# arm_sheet.net
KiCad netlist of a schematic drawn in Altium Designer
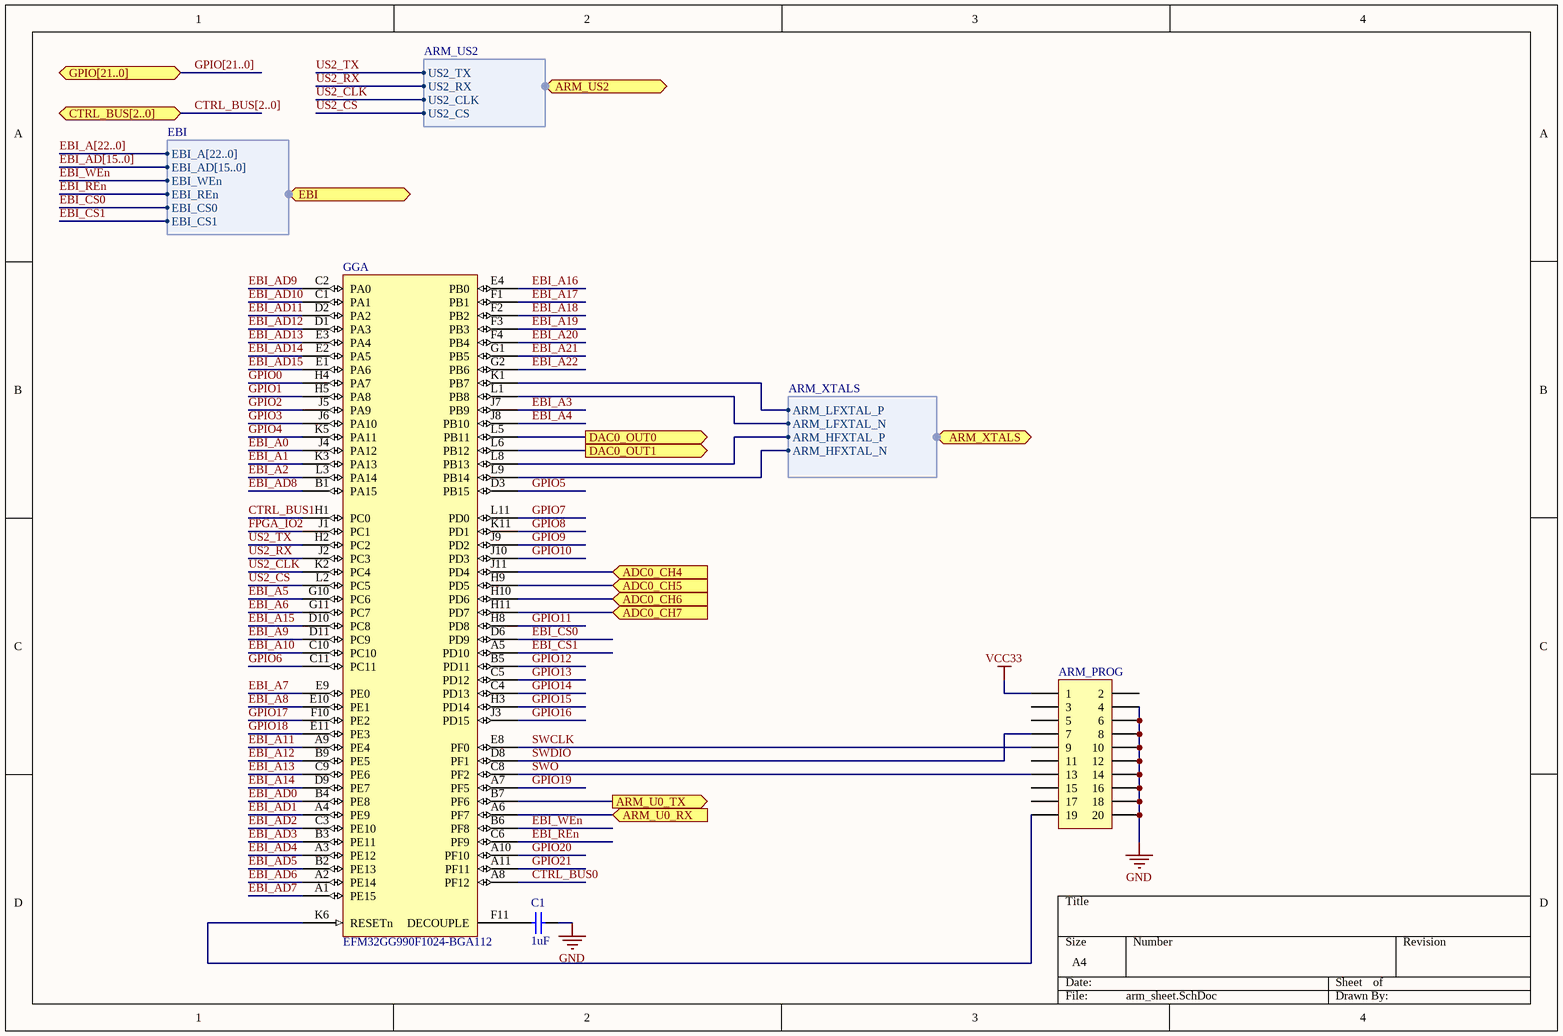
[diagram p0: arm_sheet.SchDoc]

(export (version "E")
  (design (tool "Eeschema 10.0.6"))
  (components
    (comp (ref "ARM_PROG")
      (value "Header 10X2")
      (footprint "HDR2X10")
      (description "Header, 10-Pin, Dual row")
      (fields (field (name "PUBLISHER") "Altium Limited"))
      (libsource (lib "Miscellaneous Connectors") (part "Header 10X2"))
    )
    (comp (ref "C1")
      (value "1uF")
      (footprint "CAPC0805(2012)100_N")
      (description "CAP 1uF 16V ±10% 0805 (2012 Metric) Thickness 1mm SMD")
      (fields (field (name "TOLERANCE") "±10%"))
      (libsource (lib "Altium Content Vault") (part "CMP-1036-04747-1"))
    )
    (comp (ref "GG")
      (value "EFM32GG990F1024-BGA112")
      (footprint "ENMR-BGA112")
      (fields (field (name "GENERIC PART NUMBER") "EFM32GG990"))
      (libsource (lib "Silicon Labs Energy Micro EFM32") (part "EFM32GG990F1024-BGA112"))
    )
  )
  (nets
    (net (code "5") (name "/ADC0_CH4") (class "Default")
      (node (ref "GG") (pin "J11") (pinfunction "PD4_J11") (pintype "bidirectional"))
    )
    (net (code "6") (name "/ADC0_CH5") (class "Default")
      (node (ref "GG") (pin "H9") (pinfunction "PD5_H9") (pintype "bidirectional"))
    )
    (net (code "7") (name "/ADC0_CH6") (class "Default")
      (node (ref "GG") (pin "H10") (pinfunction "PD6_H10") (pintype "bidirectional"))
    )
    (net (code "8") (name "/ADC0_CH7") (class "Default")
      (node (ref "GG") (pin "H11") (pinfunction "PD7_H11") (pintype "bidirectional"))
    )
    (net (code "9") (name "/ARM_HFXTAL_N") (class "Default")
      (node (ref "GG") (pin "L9") (pinfunction "PB14_L9") (pintype "bidirectional"))
    )
    (net (code "10") (name "/ARM_HFXTAL_P") (class "Default")
      (node (ref "GG") (pin "L8") (pinfunction "PB13_L8") (pintype "bidirectional"))
    )
    (net (code "11") (name "/ARM_LFXTAL_N") (class "Default")
      (node (ref "GG") (pin "L1") (pinfunction "PB8_L1") (pintype "bidirectional"))
    )
    (net (code "12") (name "/ARM_LFXTAL_P") (class "Default")
      (node (ref "GG") (pin "K1") (pinfunction "PB7_K1") (pintype "bidirectional"))
    )
    (net (code "13") (name "/ARM_U0_RX") (class "Default")
      (node (ref "GG") (pin "A6") (pinfunction "PF7_A6") (pintype "bidirectional"))
    )
    (net (code "14") (name "/ARM_U0_TX") (class "Default")
      (node (ref "GG") (pin "B7") (pinfunction "PF6_B7") (pintype "bidirectional"))
    )
    (net (code "15") (name "/CTRL_BUS0") (class "Default")
      (node (ref "GG") (pin "A8") (pinfunction "PF12_A8") (pintype "bidirectional"))
    )
    (net (code "16") (name "/CTRL_BUS1") (class "Default")
      (node (ref "GG") (pin "H1") (pinfunction "PC0_H1") (pintype "bidirectional"))
    )
    (net (code "18") (name "/DAC0_OUT0") (class "Default")
      (node (ref "GG") (pin "L5") (pinfunction "PB11_L5") (pintype "bidirectional"))
    )
    (net (code "19") (name "/DAC0_OUT1") (class "Default")
      (node (ref "GG") (pin "L6") (pinfunction "PB12_L6") (pintype "bidirectional"))
    )
    (net (code "20") (name "/EBI_A0") (class "Default")
      (node (ref "GG") (pin "J4") (pinfunction "PA12_J4") (pintype "bidirectional"))
    )
    (net (code "21") (name "/EBI_A1") (class "Default")
      (node (ref "GG") (pin "K3") (pinfunction "PA13_K3") (pintype "bidirectional"))
    )
    (net (code "22") (name "/EBI_A2") (class "Default")
      (node (ref "GG") (pin "L3") (pinfunction "PA14_L3") (pintype "bidirectional"))
    )
    (net (code "23") (name "/EBI_A3") (class "Default")
      (node (ref "GG") (pin "J7") (pinfunction "PB9_J7") (pintype "bidirectional"))
    )
    (net (code "24") (name "/EBI_A4") (class "Default")
      (node (ref "GG") (pin "J8") (pinfunction "PB10_J8") (pintype "bidirectional"))
    )
    (net (code "25") (name "/EBI_A5") (class "Default")
      (node (ref "GG") (pin "G10") (pinfunction "PC6_G10") (pintype "bidirectional"))
    )
    (net (code "26") (name "/EBI_A6") (class "Default")
      (node (ref "GG") (pin "G11") (pinfunction "PC7_G11") (pintype "bidirectional"))
    )
    (net (code "27") (name "/EBI_A7") (class "Default")
      (node (ref "GG") (pin "E9") (pinfunction "PE0_E9") (pintype "bidirectional"))
    )
    (net (code "28") (name "/EBI_A8") (class "Default")
      (node (ref "GG") (pin "E10") (pinfunction "PE1_E10") (pintype "bidirectional"))
    )
    (net (code "29") (name "/EBI_A9") (class "Default")
      (node (ref "GG") (pin "D11") (pinfunction "PC9_D11") (pintype "bidirectional"))
    )
    (net (code "30") (name "/EBI_A10") (class "Default")
      (node (ref "GG") (pin "C10") (pinfunction "PC10_C10") (pintype "bidirectional"))
    )
    (net (code "31") (name "/EBI_A11") (class "Default")
      (node (ref "GG") (pin "A9") (pinfunction "PE4_A9") (pintype "bidirectional"))
    )
    (net (code "32") (name "/EBI_A12") (class "Default")
      (node (ref "GG") (pin "B9") (pinfunction "PE5_B9") (pintype "bidirectional"))
    )
    (net (code "33") (name "/EBI_A13") (class "Default")
      (node (ref "GG") (pin "C9") (pinfunction "PE6_C9") (pintype "bidirectional"))
    )
    (net (code "34") (name "/EBI_A14") (class "Default")
      (node (ref "GG") (pin "D9") (pinfunction "PE7_D9") (pintype "bidirectional"))
    )
    (net (code "35") (name "/EBI_A15") (class "Default")
      (node (ref "GG") (pin "D10") (pinfunction "PC8_D10") (pintype "bidirectional"))
    )
    (net (code "36") (name "/EBI_A16") (class "Default")
      (node (ref "GG") (pin "E4") (pinfunction "PB0_E4") (pintype "bidirectional"))
    )
    (net (code "37") (name "/EBI_A17") (class "Default")
      (node (ref "GG") (pin "F1") (pinfunction "PB1_F1") (pintype "bidirectional"))
    )
    (net (code "38") (name "/EBI_A18") (class "Default")
      (node (ref "GG") (pin "F2") (pinfunction "PB2_F2") (pintype "bidirectional"))
    )
    (net (code "39") (name "/EBI_A19") (class "Default")
      (node (ref "GG") (pin "F3") (pinfunction "PB3_F3") (pintype "bidirectional"))
    )
    (net (code "40") (name "/EBI_A20") (class "Default")
      (node (ref "GG") (pin "F4") (pinfunction "PB4_F4") (pintype "bidirectional"))
    )
    (net (code "41") (name "/EBI_A21") (class "Default")
      (node (ref "GG") (pin "G1") (pinfunction "PB5_G1") (pintype "bidirectional"))
    )
    (net (code "42") (name "/EBI_A22") (class "Default")
      (node (ref "GG") (pin "G2") (pinfunction "PB6_G2") (pintype "bidirectional"))
    )
    (net (code "43") (name "/EBI_AD0") (class "Default")
      (node (ref "GG") (pin "B4") (pinfunction "PE8_B4") (pintype "bidirectional"))
    )
    (net (code "44") (name "/EBI_AD1") (class "Default")
      (node (ref "GG") (pin "A4") (pinfunction "PE9_A4") (pintype "bidirectional"))
    )
    (net (code "45") (name "/EBI_AD2") (class "Default")
      (node (ref "GG") (pin "C3") (pinfunction "PE10_C3") (pintype "bidirectional"))
    )
    (net (code "46") (name "/EBI_AD3") (class "Default")
      (node (ref "GG") (pin "B3") (pinfunction "PE11_B3") (pintype "bidirectional"))
    )
    (net (code "47") (name "/EBI_AD4") (class "Default")
      (node (ref "GG") (pin "A3") (pinfunction "PE12_A3") (pintype "bidirectional"))
    )
    (net (code "48") (name "/EBI_AD5") (class "Default")
      (node (ref "GG") (pin "B2") (pinfunction "PE13_B2") (pintype "bidirectional"))
    )
    (net (code "49") (name "/EBI_AD6") (class "Default")
      (node (ref "GG") (pin "A2") (pinfunction "PE14_A2") (pintype "bidirectional"))
    )
    (net (code "50") (name "/EBI_AD7") (class "Default")
      (node (ref "GG") (pin "A1") (pinfunction "PE15_A1") (pintype "bidirectional"))
    )
    (net (code "51") (name "/EBI_AD8") (class "Default")
      (node (ref "GG") (pin "B1") (pinfunction "PA15_B1") (pintype "bidirectional"))
    )
    (net (code "52") (name "/EBI_AD9") (class "Default")
      (node (ref "GG") (pin "C2") (pinfunction "PA0_C2") (pintype "bidirectional"))
    )
    (net (code "53") (name "/EBI_AD10") (class "Default")
      (node (ref "GG") (pin "C1") (pinfunction "PA1_C1") (pintype "bidirectional"))
    )
    (net (code "54") (name "/EBI_AD11") (class "Default")
      (node (ref "GG") (pin "D2") (pinfunction "PA2_D2") (pintype "bidirectional"))
    )
    (net (code "55") (name "/EBI_AD12") (class "Default")
      (node (ref "GG") (pin "D1") (pinfunction "PA3_D1") (pintype "bidirectional"))
    )
    (net (code "56") (name "/EBI_AD13") (class "Default")
      (node (ref "GG") (pin "E3") (pinfunction "PA4_E3") (pintype "bidirectional"))
    )
    (net (code "57") (name "/EBI_AD14") (class "Default")
      (node (ref "GG") (pin "E2") (pinfunction "PA5_E2") (pintype "bidirectional"))
    )
    (net (code "58") (name "/EBI_AD15") (class "Default")
      (node (ref "GG") (pin "E1") (pinfunction "PA6_E1") (pintype "bidirectional"))
    )
    (net (code "60") (name "/EBI_CS0") (class "Default")
      (node (ref "GG") (pin "D6") (pinfunction "PD9_D6") (pintype "bidirectional"))
    )
    (net (code "61") (name "/EBI_CS1") (class "Default")
      (node (ref "GG") (pin "A5") (pinfunction "PD10_A5") (pintype "bidirectional"))
    )
    (net (code "62") (name "/EBI_REn") (class "Default")
      (node (ref "GG") (pin "C6") (pinfunction "PF9_C6") (pintype "bidirectional"))
    )
    (net (code "63") (name "/EBI_WEn") (class "Default")
      (node (ref "GG") (pin "B6") (pinfunction "PF8_B6") (pintype "bidirectional"))
    )
    (net (code "65") (name "/FPGA_IO2") (class "Default")
      (node (ref "GG") (pin "J1") (pinfunction "PC1_J1") (pintype "bidirectional"))
    )
    (net (code "66") (name "/GPIO0") (class "Default")
      (node (ref "GG") (pin "H4") (pinfunction "PA7_H4") (pintype "bidirectional"))
    )
    (net (code "67") (name "/GPIO1") (class "Default")
      (node (ref "GG") (pin "H5") (pinfunction "PA8_H5") (pintype "bidirectional"))
    )
    (net (code "68") (name "/GPIO2") (class "Default")
      (node (ref "GG") (pin "J5") (pinfunction "PA9_J5") (pintype "bidirectional"))
    )
    (net (code "69") (name "/GPIO3") (class "Default")
      (node (ref "GG") (pin "J6") (pinfunction "PA10_J6") (pintype "bidirectional"))
    )
    (net (code "70") (name "/GPIO4") (class "Default")
      (node (ref "GG") (pin "K5") (pinfunction "PA11_K5") (pintype "bidirectional"))
    )
    (net (code "71") (name "/GPIO5") (class "Default")
      (node (ref "GG") (pin "D3") (pinfunction "PB15_D3") (pintype "bidirectional"))
    )
    (net (code "72") (name "/GPIO6") (class "Default")
      (node (ref "GG") (pin "C11") (pinfunction "PC11_C11") (pintype "bidirectional"))
    )
    (net (code "73") (name "/GPIO7") (class "Default")
      (node (ref "GG") (pin "L11") (pinfunction "PD0_L11") (pintype "bidirectional"))
    )
    (net (code "74") (name "/GPIO8") (class "Default")
      (node (ref "GG") (pin "K11") (pinfunction "PD1_K11") (pintype "bidirectional"))
    )
    (net (code "75") (name "/GPIO9") (class "Default")
      (node (ref "GG") (pin "J9") (pinfunction "PD2_J9") (pintype "bidirectional"))
    )
    (net (code "76") (name "/GPIO10") (class "Default")
      (node (ref "GG") (pin "J10") (pinfunction "PD3_J10") (pintype "bidirectional"))
    )
    (net (code "77") (name "/GPIO11") (class "Default")
      (node (ref "GG") (pin "H8") (pinfunction "PD8_H8") (pintype "bidirectional"))
    )
    (net (code "78") (name "/GPIO12") (class "Default")
      (node (ref "GG") (pin "B5") (pinfunction "PD11_B5") (pintype "bidirectional"))
    )
    (net (code "79") (name "/GPIO13") (class "Default")
      (node (ref "GG") (pin "C5") (pinfunction "PD12_C5") (pintype "bidirectional"))
    )
    (net (code "80") (name "/GPIO14") (class "Default")
      (node (ref "GG") (pin "C4") (pinfunction "PD13_C4") (pintype "bidirectional"))
    )
    (net (code "81") (name "/GPIO15") (class "Default")
      (node (ref "GG") (pin "H3") (pinfunction "PD14_H3") (pintype "bidirectional"))
    )
    (net (code "82") (name "/GPIO16") (class "Default")
      (node (ref "GG") (pin "J3") (pinfunction "PD15_J3") (pintype "bidirectional"))
    )
    (net (code "83") (name "/GPIO17") (class "Default")
      (node (ref "GG") (pin "F10") (pinfunction "PE2_F10") (pintype "bidirectional"))
    )
    (net (code "84") (name "/GPIO18") (class "Default")
      (node (ref "GG") (pin "E11") (pinfunction "PE3_E11") (pintype "bidirectional"))
    )
    (net (code "85") (name "/GPIO19") (class "Default")
      (node (ref "GG") (pin "A7") (pinfunction "PF5_A7") (pintype "bidirectional"))
    )
    (net (code "86") (name "/GPIO20") (class "Default")
      (node (ref "GG") (pin "A10") (pinfunction "PF10_A10") (pintype "bidirectional"))
    )
    (net (code "87") (name "/GPIO21") (class "Default")
      (node (ref "GG") (pin "A11") (pinfunction "PF11_A11") (pintype "bidirectional"))
    )
    (net (code "89") (name "/SWCLK") (class "Default")
      (node (ref "ARM_PROG") (pin "9") (pinfunction "9_9") (pintype "passive"))
      (node (ref "GG") (pin "E8") (pinfunction "PF0_E8") (pintype "bidirectional"))
    )
    (net (code "90") (name "/SWDIO") (class "Default")
      (node (ref "ARM_PROG") (pin "7") (pinfunction "7_7") (pintype "passive"))
      (node (ref "GG") (pin "D8") (pinfunction "PF1_D8") (pintype "bidirectional"))
    )
    (net (code "91") (name "/SWO") (class "Default")
      (node (ref "ARM_PROG") (pin "13") (pinfunction "13_13") (pintype "passive"))
      (node (ref "GG") (pin "C8") (pinfunction "PF2_C8") (pintype "bidirectional"))
    )
    (net (code "92") (name "/US2_CLK") (class "Default")
      (node (ref "GG") (pin "K2") (pinfunction "PC4_K2") (pintype "bidirectional"))
    )
    (net (code "93") (name "/US2_CS") (class "Default")
      (node (ref "GG") (pin "L2") (pinfunction "PC5_L2") (pintype "bidirectional"))
    )
    (net (code "94") (name "/US2_RX") (class "Default")
      (node (ref "GG") (pin "J2") (pinfunction "PC3_J2") (pintype "bidirectional"))
    )
    (net (code "95") (name "/US2_TX") (class "Default")
      (node (ref "GG") (pin "H2") (pinfunction "PC2_H2") (pintype "bidirectional"))
    )
    (net (code "99") (name "GND") (class "Default")
      (node (ref "ARM_PROG") (pin "10") (pinfunction "10_10") (pintype "passive"))
      (node (ref "ARM_PROG") (pin "12") (pinfunction "12_12") (pintype "passive"))
      (node (ref "ARM_PROG") (pin "14") (pinfunction "14_14") (pintype "passive"))
      (node (ref "ARM_PROG") (pin "16") (pinfunction "16_16") (pintype "passive"))
      (node (ref "ARM_PROG") (pin "18") (pinfunction "18_18") (pintype "passive"))
      (node (ref "ARM_PROG") (pin "20") (pinfunction "20_20") (pintype "passive"))
      (node (ref "ARM_PROG") (pin "4") (pinfunction "4_4") (pintype "passive"))
      (node (ref "ARM_PROG") (pin "6") (pinfunction "6_6") (pintype "passive"))
      (node (ref "ARM_PROG") (pin "8") (pinfunction "8_8") (pintype "passive"))
      (node (ref "C1") (pin "2") (pinfunction "2_2") (pintype "passive"))
    )
    (net (code "100") (name "Net-(GGA-DECOUPLE)") (class "Default")
      (node (ref "C1") (pin "1") (pinfunction "1_1") (pintype "passive"))
      (node (ref "GG") (pin "F11") (pinfunction "DECOUPLE_F11") (pintype "passive"))
    )
    (net (code "101") (name "Net-(GGA-RESETn)") (class "Default")
      (node (ref "ARM_PROG") (pin "19") (pinfunction "19_19") (pintype "passive"))
      (node (ref "GG") (pin "K6") (pinfunction "RESETn_K6") (pintype "input"))
    )
    (net (code "102") (name "VCC33") (class "Default")
      (node (ref "ARM_PROG") (pin "1") (pinfunction "1_1") (pintype "passive"))
    )
    (net (code "103") (name "unconnected-(ARM_PROG-Pad2)") (class "Default")
      (node (ref "ARM_PROG") (pin "2") (pinfunction "2_2") (pintype "passive"))
    )
    (net (code "104") (name "unconnected-(ARM_PROG-Pad3)") (class "Default")
      (node (ref "ARM_PROG") (pin "3") (pinfunction "3_3") (pintype "passive"))
    )
    (net (code "105") (name "unconnected-(ARM_PROG-Pad5)") (class "Default")
      (node (ref "ARM_PROG") (pin "5") (pinfunction "5_5") (pintype "passive"))
    )
    (net (code "106") (name "unconnected-(ARM_PROG-Pad11)") (class "Default")
      (node (ref "ARM_PROG") (pin "11") (pinfunction "11_11") (pintype "passive"))
    )
    (net (code "107") (name "unconnected-(ARM_PROG-Pad15)") (class "Default")
      (node (ref "ARM_PROG") (pin "15") (pinfunction "15_15") (pintype "passive"))
    )
    (net (code "108") (name "unconnected-(ARM_PROG-Pad17)") (class "Default")
      (node (ref "ARM_PROG") (pin "17") (pinfunction "17_17") (pintype "passive"))
    )
  )
)
